# SCH_Proyecto1_2023-10-21.net
KiCad netlist of a schematic drawn in EasyEDA
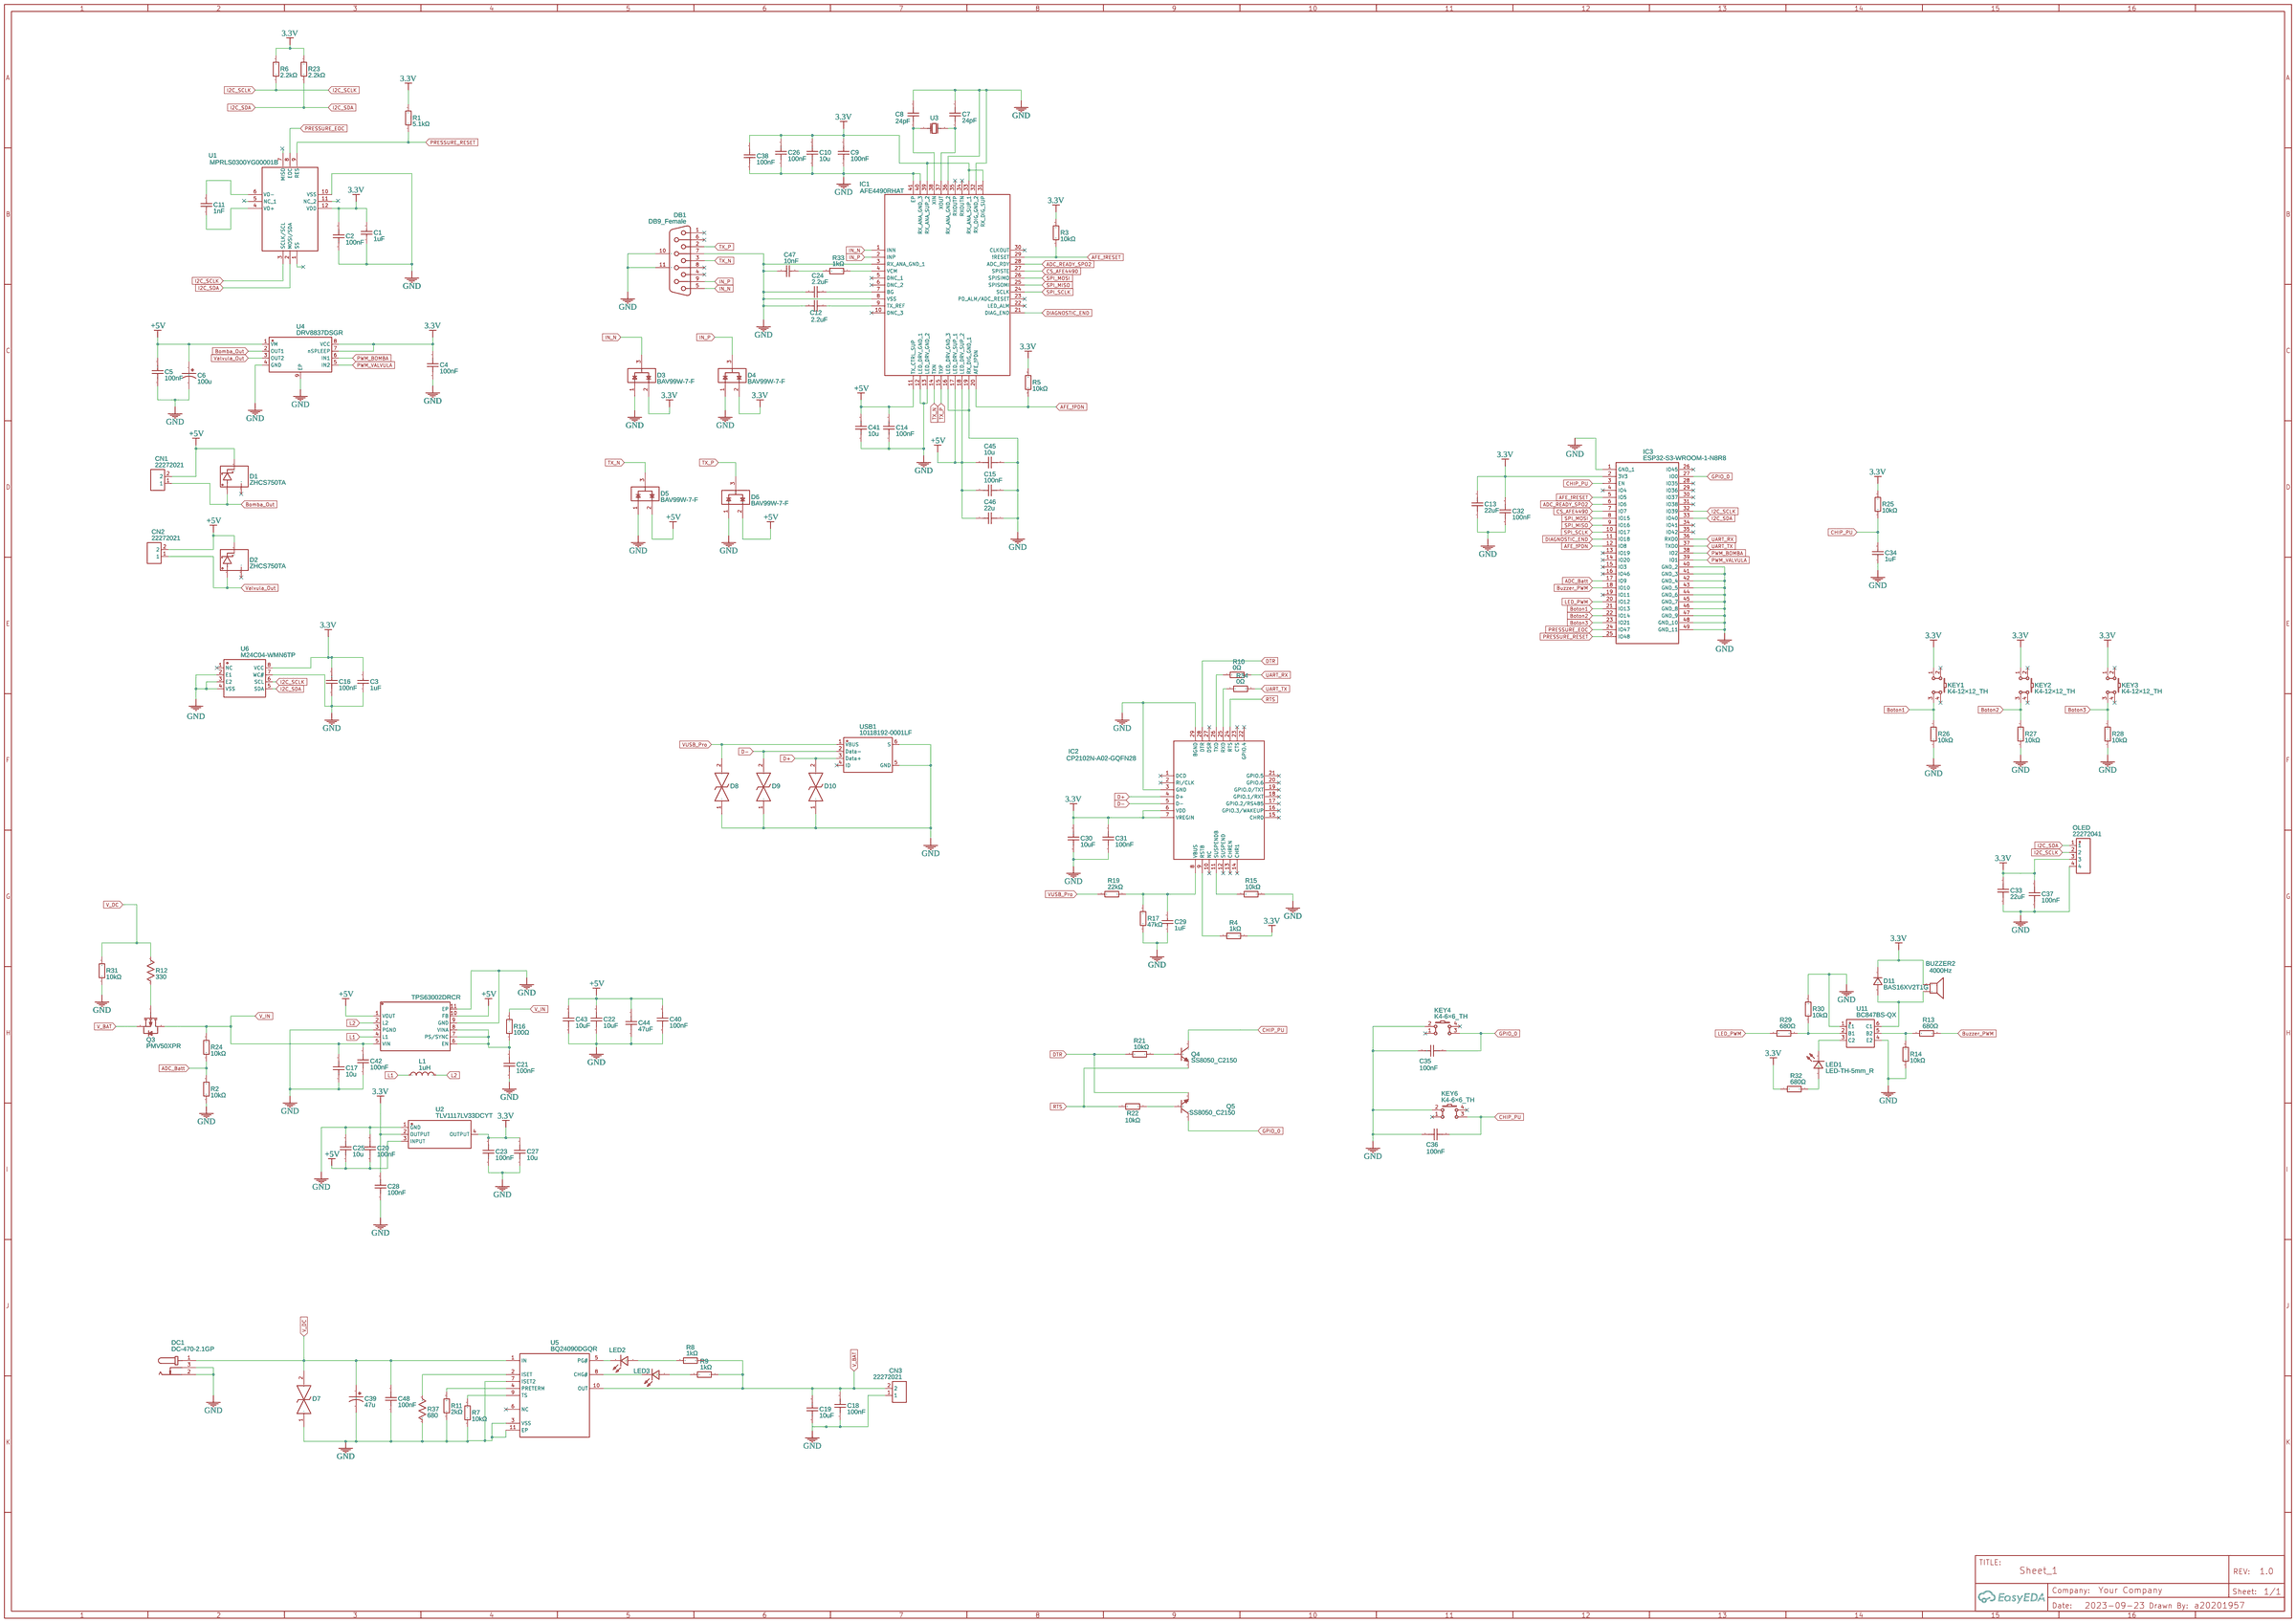
[diagram p0: schematic sheet]

(export (version "E")
  (design (tool "Eeschema 10.0.6"))
  (components
    (comp (ref "BUZZER2")
      (value "4000Hz")
      (fields (field (name "Manufacturer Part") "SFN-1407PA7.6") (field (name "Manufacturer") "S&S(海旭)"))
      (libsource (lib "") (part "SFN-1407PA7.6"))
    )
    (comp (ref "C1")
      (value "1uF")
      (fields
        (field (name "Manufacturer Part") "CL10A105KB8NNNC")
        (field (name "Manufacturer") "SAMSUNG(三星)")
      )
      (libsource (lib "") (part "CL10A105KB8NNNC"))
    )
    (comp (ref "C2")
      (value "100nF")
      (fields
        (field (name "Manufacturer Part") "CC0603KRX7R9BB104")
        (field (name "Manufacturer") "YAGEO(国巨)")
      )
      (libsource (lib "") (part "CC0603KRX7R9BB104"))
    )
    (comp (ref "C3")
      (value "1uF")
      (fields
        (field (name "Manufacturer Part") "CL10A105KB8NNNC")
        (field (name "Manufacturer") "SAMSUNG(三星)")
      )
      (libsource (lib "") (part "CL10A105KB8NNNC"))
    )
    (comp (ref "C4")
      (value "100nF")
      (fields
        (field (name "Manufacturer Part") "CC0603KRX7R9BB104")
        (field (name "Manufacturer") "YAGEO(国巨)")
      )
      (libsource (lib "") (part "CC0603KRX7R9BB104"))
    )
    (comp (ref "C5")
      (value "100nF")
      (fields
        (field (name "Manufacturer Part") "CC0603KRX7R9BB104")
        (field (name "Manufacturer") "YAGEO(国巨)")
      )
      (libsource (lib "") (part "CC0603KRX7R9BB104"))
    )
    (comp (ref "C6") (value "100u") (libsource (lib "") (part "CE_TH_D5.0×F2.0_US_1")))
    (comp (ref "C7") (value "24pF") (libsource (lib "") (part "C_0603_US")))
    (comp (ref "C8") (value "24pF") (libsource (lib "") (part "C_0603_US")))
    (comp (ref "C9")
      (value "100nF")
      (fields
        (field (name "Manufacturer Part") "CC0603KRX7R9BB104")
        (field (name "Manufacturer") "YAGEO(国巨)")
      )
      (libsource (lib "") (part "CC0603KRX7R9BB104"))
    )
    (comp (ref "C10") (value "10u") (libsource (lib "") (part "C_0805_US")))
    (comp (ref "C11")
      (value "1nF")
      (fields
        (field (name "Manufacturer Part") "CL10B102KB8NNNC")
        (field (name "Manufacturer") "SAMSUNG(三星)")
      )
      (libsource (lib "") (part "CL10B102KB8NNNC"))
    )
    (comp (ref "C12")
      (value "2.2uF")
      (fields
        (field (name "Manufacturer Part") "CL10A225KO8NNNC")
        (field (name "Manufacturer") "SAMSUNG(三星)")
      )
      (libsource (lib "") (part "CL10A225KO8NNNC"))
    )
    (comp (ref "C13")
      (value "22uF")
      (fields
        (field (name "Manufacturer Part") "CL21A226MAQNNNE")
        (field (name "Manufacturer") "SAMSUNG(三星)")
      )
      (libsource (lib "") (part "CL21A226MAQNNNE"))
    )
    (comp (ref "C14")
      (value "100nF")
      (fields
        (field (name "Manufacturer Part") "CC0603KRX7R9BB104")
        (field (name "Manufacturer") "YAGEO(国巨)")
      )
      (libsource (lib "") (part "CC0603KRX7R9BB104"))
    )
    (comp (ref "C15")
      (value "100nF")
      (fields
        (field (name "Manufacturer Part") "CC0603KRX7R9BB104")
        (field (name "Manufacturer") "YAGEO(国巨)")
      )
      (libsource (lib "") (part "CC0603KRX7R9BB104_1"))
    )
    (comp (ref "C16")
      (value "100nF")
      (fields
        (field (name "Manufacturer Part") "CC0603KRX7R9BB104")
        (field (name "Manufacturer") "YAGEO(国巨)")
      )
      (libsource (lib "") (part "CC0603KRX7R9BB104"))
    )
    (comp (ref "C17") (value "10u") (libsource (lib "") (part "C_0805_US")))
    (comp (ref "C18")
      (value "100nF")
      (fields
        (field (name "Manufacturer Part") "CC0603KRX7R9BB104")
        (field (name "Manufacturer") "YAGEO(国巨)")
      )
      (libsource (lib "") (part "CC0603KRX7R9BB104"))
    )
    (comp (ref "C19") (value "10uF") (libsource (lib "") (part "C_0805_US")))
    (comp (ref "C20")
      (value "100nF")
      (fields
        (field (name "Manufacturer Part") "CC0603KRX7R9BB104")
        (field (name "Manufacturer") "YAGEO(国巨)")
      )
      (libsource (lib "") (part "CC0603KRX7R9BB104"))
    )
    (comp (ref "C21")
      (value "100nF")
      (fields
        (field (name "Manufacturer Part") "CC0603KRX7R9BB104")
        (field (name "Manufacturer") "YAGEO(国巨)")
      )
      (libsource (lib "") (part "CC0603KRX7R9BB104"))
    )
    (comp (ref "C22") (value "10uF") (libsource (lib "") (part "C_0805_US")))
    (comp (ref "C23")
      (value "100nF")
      (fields
        (field (name "Manufacturer Part") "CC0603KRX7R9BB104")
        (field (name "Manufacturer") "YAGEO(国巨)")
      )
      (libsource (lib "") (part "CC0603KRX7R9BB104"))
    )
    (comp (ref "C24")
      (value "2.2uF")
      (fields
        (field (name "Manufacturer Part") "CL10A225KO8NNNC")
        (field (name "Manufacturer") "SAMSUNG(三星)")
      )
      (libsource (lib "") (part "CL10A225KO8NNNC"))
    )
    (comp (ref "C25") (value "10u") (libsource (lib "") (part "C_0805_US")))
    (comp (ref "C26")
      (value "100nF")
      (fields
        (field (name "Manufacturer Part") "CC0603KRX7R9BB104")
        (field (name "Manufacturer") "YAGEO(国巨)")
      )
      (libsource (lib "") (part "CC0603KRX7R9BB104"))
    )
    (comp (ref "C27") (value "10u") (libsource (lib "") (part "C_0805_US")))
    (comp (ref "C28")
      (value "100nF")
      (fields
        (field (name "Manufacturer Part") "CC0603KRX7R9BB104")
        (field (name "Manufacturer") "YAGEO(国巨)")
      )
      (libsource (lib "") (part "CC0603KRX7R9BB104"))
    )
    (comp (ref "C29")
      (value "1uF")
      (fields
        (field (name "Manufacturer Part") "CL10A105KB8NNNC")
        (field (name "Manufacturer") "SAMSUNG(三星)")
      )
      (libsource (lib "") (part "CL10A105KB8NNNC"))
    )
    (comp (ref "C30") (value "10uF") (libsource (lib "") (part "C_0805_US")))
    (comp (ref "C31")
      (value "100nF")
      (fields
        (field (name "Manufacturer Part") "CC0603KRX7R9BB104")
        (field (name "Manufacturer") "YAGEO(国巨)")
      )
      (libsource (lib "") (part "CC0603KRX7R9BB104"))
    )
    (comp (ref "C32")
      (value "100nF")
      (fields
        (field (name "Manufacturer Part") "CC0603KRX7R9BB104")
        (field (name "Manufacturer") "YAGEO(国巨)")
      )
      (libsource (lib "") (part "CC0603KRX7R9BB104"))
    )
    (comp (ref "C33")
      (value "22uF")
      (fields
        (field (name "Manufacturer Part") "CL21A226MAQNNNE")
        (field (name "Manufacturer") "SAMSUNG(三星)")
      )
      (libsource (lib "") (part "CL21A226MAQNNNE"))
    )
    (comp (ref "C34")
      (value "1uF")
      (fields
        (field (name "Manufacturer Part") "CL10A105KB8NNNC")
        (field (name "Manufacturer") "SAMSUNG(三星)")
      )
      (libsource (lib "") (part "CL10A105KB8NNNC"))
    )
    (comp (ref "C35")
      (value "100nF")
      (fields
        (field (name "Manufacturer Part") "CC0603KRX7R9BB104")
        (field (name "Manufacturer") "YAGEO(国巨)")
      )
      (libsource (lib "") (part "CC0603KRX7R9BB104_1"))
    )
    (comp (ref "C36")
      (value "100nF")
      (fields
        (field (name "Manufacturer Part") "CC0603KRX7R9BB104")
        (field (name "Manufacturer") "YAGEO(国巨)")
      )
      (libsource (lib "") (part "CC0603KRX7R9BB104_1"))
    )
    (comp (ref "C37")
      (value "100nF")
      (fields
        (field (name "Manufacturer Part") "CC0603KRX7R9BB104")
        (field (name "Manufacturer") "YAGEO(国巨)")
      )
      (libsource (lib "") (part "CC0603KRX7R9BB104"))
    )
    (comp (ref "C38")
      (value "100nF")
      (fields
        (field (name "Manufacturer Part") "CC0603KRX7R9BB104")
        (field (name "Manufacturer") "YAGEO(国巨)")
      )
      (libsource (lib "") (part "CC0603KRX7R9BB104"))
    )
    (comp (ref "C39") (value "47u") (libsource (lib "") (part "CE_TH_D5.0×F2.0_US")))
    (comp (ref "C40")
      (value "100nF")
      (fields
        (field (name "Manufacturer Part") "CC0603KRX7R9BB104")
        (field (name "Manufacturer") "YAGEO(国巨)")
      )
      (libsource (lib "") (part "CC0603KRX7R9BB104"))
    )
    (comp (ref "C41") (value "10u") (libsource (lib "") (part "C_0805_US")))
    (comp (ref "C42")
      (value "100nF")
      (fields
        (field (name "Manufacturer Part") "CC0603KRX7R9BB104")
        (field (name "Manufacturer") "YAGEO(国巨)")
      )
      (libsource (lib "") (part "CC0603KRX7R9BB104"))
    )
    (comp (ref "C43") (value "10uF") (libsource (lib "") (part "C_0805_US")))
    (comp (ref "C44")
      (value "47uF")
      (fields
        (field (name "Manufacturer Part") "CL31A476MPHNNNE")
        (field (name "Manufacturer") "SAMSUNG(三星)")
      )
      (libsource (lib "") (part "CL31A476MPHNNNE"))
    )
    (comp (ref "C45") (value "10u") (libsource (lib "") (part "C_0805_US_1")))
    (comp (ref "C46") (value "22u") (libsource (lib "") (part "C_0603_US_1")))
    (comp (ref "C47")
      (value "10nF")
      (fields (field (name "Manufacturer Part") "0603B103K500NT") (field (name "Manufacturer") "FH(风华)"))
      (libsource (lib "") (part "0603B103K500NT"))
    )
    (comp (ref "C48")
      (value "100nF")
      (fields
        (field (name "Manufacturer Part") "CC0603KRX7R9BB104")
        (field (name "Manufacturer") "YAGEO(国巨)")
      )
      (libsource (lib "") (part "CC0603KRX7R9BB104"))
    )
    (comp (ref "CN1")
      (value "22272021")
      (fields (field (name "Manufacturer") "MOLEX"))
      (libsource (lib "") (part "22272021_1"))
    )
    (comp (ref "CN2")
      (value "22272021")
      (fields (field (name "Manufacturer") "MOLEX"))
      (libsource (lib "") (part "22272021_1"))
    )
    (comp (ref "CN3")
      (value "22272021")
      (fields (field (name "Manufacturer") "MOLEX"))
      (libsource (lib "") (part "22272021"))
    )
    (comp (ref "D1")
      (value "ZHCS750TA")
      (fields (field (name "Manufacturer") "DIODES(美台)"))
      (libsource (lib "") (part "ZHCS750TA"))
    )
    (comp (ref "D2")
      (value "ZHCS750TA")
      (fields (field (name "Manufacturer") "DIODES(美台)"))
      (libsource (lib "") (part "ZHCS750TA"))
    )
    (comp (ref "D3")
      (value "BAV99W-7-F")
      (fields (field (name "Manufacturer") "DIODES(美台)"))
      (libsource (lib "") (part "BAV99W-7-F"))
    )
    (comp (ref "D4")
      (value "BAV99W-7-F")
      (fields (field (name "Manufacturer") "DIODES(美台)"))
      (libsource (lib "") (part "BAV99W-7-F"))
    )
    (comp (ref "D5")
      (value "BAV99W-7-F")
      (fields (field (name "Manufacturer") "DIODES(美台)"))
      (libsource (lib "") (part "BAV99W-7-F"))
    )
    (comp (ref "D6")
      (value "BAV99W-7-F")
      (fields (field (name "Manufacturer") "DIODES(美台)"))
      (libsource (lib "") (part "BAV99W-7-F"))
    )
    (comp (ref "D7") (value "CPDQ5V0-HF") (libsource (lib "") (part "CPDQ5V0-HF")))
    (comp (ref "D8") (value "CPDQ5V0-HF") (libsource (lib "") (part "CPDQ5V0-HF")))
    (comp (ref "D9") (value "CPDQ5V0-HF") (libsource (lib "") (part "CPDQ5V0-HF")))
    (comp (ref "D10") (value "CPDQ5V0-HF") (libsource (lib "") (part "CPDQ5V0-HF")))
    (comp (ref "D11")
      (value "BAS16XV2T1G")
      (fields (field (name "Manufacturer") "onsemi(安森美)"))
      (libsource (lib "") (part "BAS16XV2T1G"))
    )
    (comp (ref "DB1")
      (value "DB9_Female")
      (fields (field (name "Manufacturer") "Ckmtw(灿科盟)"))
      (libsource (lib "") (part "DB9_Female"))
    )
    (comp (ref "DC1")
      (value "DC-470-2.1GP")
      (fields (field (name "Manufacturer") "GANGYUAN"))
      (libsource (lib "") (part "DC-470-2.1GP"))
    )
    (comp (ref "IC1") (value "AFE4490RHAT") (libsource (lib "") (part "AFE4490RHAT")))
    (comp (ref "IC2") (value "CP2102N-A02-GQFN28") (libsource (lib "") (part "CP2102N-A02-GQFN28")))
    (comp (ref "IC3") (value "ESP32-S3-WROOM-1-N8R8") (libsource (lib "") (part "ESP32-S3-WROOM-1-N8R8")))
    (comp (ref "KEY1")
      (value "K4-12×12_TH")
      (fields (field (name "Manufacturer Part") "K2-1103DP-M4SW-04") (field (name "Manufacturer") "韩国韩荣"))
      (libsource (lib "") (part "K4-12×12_TH"))
    )
    (comp (ref "KEY2")
      (value "K4-12×12_TH")
      (fields (field (name "Manufacturer Part") "K2-1103DP-M4SW-04") (field (name "Manufacturer") "韩国韩荣"))
      (libsource (lib "") (part "K4-12×12_TH"))
    )
    (comp (ref "KEY3")
      (value "K4-12×12_TH")
      (fields (field (name "Manufacturer Part") "K2-1103DP-M4SW-04") (field (name "Manufacturer") "韩国韩荣"))
      (libsource (lib "") (part "K4-12×12_TH"))
    )
    (comp (ref "KEY4")
      (value "K4-6×6_TH")
      (fields (field (name "Manufacturer Part") "K2-1102DP-E4SW-04") (field (name "Manufacturer") "韩国韩荣"))
      (libsource (lib "") (part "K4-6×6_TH"))
    )
    (comp (ref "KEY6")
      (value "K4-6×6_TH")
      (fields (field (name "Manufacturer Part") "K2-1102DP-E4SW-04") (field (name "Manufacturer") "韩国韩荣"))
      (libsource (lib "") (part "K4-6×6_TH"))
    )
    (comp (ref "L1")
      (value "1uH")
      (fields
        (field (name "Manufacturer Part") "NR3015T1R0N")
        (field (name "Manufacturer") "TAIYO YUDEN(太诱)")
      )
      (libsource (lib "") (part "NR3015T1R0N"))
    )
    (comp (ref "LED1")
      (value "LED-TH-5mm_R")
      (fields
        (field (name "Manufacturer Part") "333-2SURD/S530-A3")
        (field (name "Manufacturer") "EVERLIGHT(台湾亿光)")
      )
      (libsource (lib "") (part "LED-TH-5mm_R"))
    )
    (comp (ref "LED2")
      (value "LED-TH-5mm_R")
      (fields
        (field (name "Manufacturer Part") "333-2SURD/S530-A3")
        (field (name "Manufacturer") "EVERLIGHT(台湾亿光)")
      )
      (libsource (lib "") (part "LED-TH-5mm_R_1"))
    )
    (comp (ref "LED3")
      (value "LED-TH-5mm_G")
      (fields
        (field (name "Manufacturer Part") "333-2SYGD/S530-E2")
        (field (name "Manufacturer") "EVERLIGHT(台湾亿光)")
      )
      (libsource (lib "") (part "LED-TH-5mm_G"))
    )
    (comp (ref "OLED")
      (value "22272041")
      (fields (field (name "Manufacturer") "MOLEX"))
      (libsource (lib "") (part "22272041"))
    )
    (comp (ref "Q3")
      (value "PMV50XPR")
      (fields (field (name "Manufacturer") "Nexperia(安世)"))
      (libsource (lib "") (part "PMV50XPR"))
    )
    (comp (ref "Q4")
      (value "SS8050_C2150")
      (fields (field (name "Manufacturer Part") "SS8050") (field (name "Manufacturer") "CJ(江苏长电/长晶)"))
      (libsource (lib "") (part "SS8050_C2150_1"))
    )
    (comp (ref "Q5")
      (value "SS8050_C2150")
      (fields (field (name "Manufacturer Part") "SS8050") (field (name "Manufacturer") "CJ(江苏长电/长晶)"))
      (libsource (lib "") (part "SS8050_C2150"))
    )
    (comp (ref "R1")
      (value "5.1kΩ")
      (fields
        (field (name "Manufacturer Part") "0603WAF5101T5E")
        (field (name "Manufacturer") "UNI-ROYAL(厚声)")
      )
      (libsource (lib "") (part "0603WAF5101T5E"))
    )
    (comp (ref "R2")
      (value "10kΩ")
      (fields
        (field (name "Manufacturer Part") "0603WAF1002T5E")
        (field (name "Manufacturer") "UNI-ROYAL(厚声)")
      )
      (libsource (lib "") (part "0603WAF1002T5E"))
    )
    (comp (ref "R3")
      (value "10kΩ")
      (fields
        (field (name "Manufacturer Part") "0603WAF1002T5E")
        (field (name "Manufacturer") "UNI-ROYAL(厚声)")
      )
      (libsource (lib "") (part "0603WAF1002T5E"))
    )
    (comp (ref "R4")
      (value "1kΩ")
      (fields
        (field (name "Manufacturer Part") "0603WAF1001T5E")
        (field (name "Manufacturer") "UNI-ROYAL(厚声)")
      )
      (libsource (lib "") (part "0603WAF1001T5E"))
    )
    (comp (ref "R5")
      (value "10kΩ")
      (fields
        (field (name "Manufacturer Part") "0603WAF1002T5E")
        (field (name "Manufacturer") "UNI-ROYAL(厚声)")
      )
      (libsource (lib "") (part "0603WAF1002T5E"))
    )
    (comp (ref "R6")
      (value "2.2kΩ")
      (fields
        (field (name "Manufacturer Part") "0603WAF2201T5E")
        (field (name "Manufacturer") "UNI-ROYAL(厚声)")
      )
      (libsource (lib "") (part "0603WAF2201T5E"))
    )
    (comp (ref "R7")
      (value "10kΩ")
      (fields
        (field (name "Manufacturer Part") "0603WAF1002T5E")
        (field (name "Manufacturer") "UNI-ROYAL(厚声)")
      )
      (libsource (lib "") (part "0603WAF1002T5E"))
    )
    (comp (ref "R8")
      (value "1kΩ")
      (fields
        (field (name "Manufacturer Part") "0603WAF1001T5E")
        (field (name "Manufacturer") "UNI-ROYAL(厚声)")
      )
      (libsource (lib "") (part "0603WAF1001T5E"))
    )
    (comp (ref "R9")
      (value "1kΩ")
      (fields
        (field (name "Manufacturer Part") "0603WAF1001T5E")
        (field (name "Manufacturer") "UNI-ROYAL(厚声)")
      )
      (libsource (lib "") (part "0603WAF1001T5E"))
    )
    (comp (ref "R10")
      (value "0Ω")
      (fields
        (field (name "Manufacturer Part") "1206W4F0000T5E")
        (field (name "Manufacturer") "UNI-ROYAL(厚声)")
      )
      (libsource (lib "") (part "1206W4F0000T5E"))
    )
    (comp (ref "R11")
      (value "2kΩ")
      (fields
        (field (name "Manufacturer Part") "0603WAF2001T5E")
        (field (name "Manufacturer") "UNI-ROYAL(厚声)")
      )
      (libsource (lib "") (part "0603WAF2001T5E"))
    )
    (comp (ref "R12") (value "330") (libsource (lib "") (part "R_1206_US")))
    (comp (ref "R13")
      (value "680Ω")
      (fields
        (field (name "Manufacturer Part") "0603WAF6800T5E")
        (field (name "Manufacturer") "UNI-ROYAL(厚声)")
      )
      (libsource (lib "") (part "0603WAF6800T5E"))
    )
    (comp (ref "R14")
      (value "10kΩ")
      (fields
        (field (name "Manufacturer Part") "0603WAF1002T5E")
        (field (name "Manufacturer") "UNI-ROYAL(厚声)")
      )
      (libsource (lib "") (part "0603WAF1002T5E"))
    )
    (comp (ref "R15")
      (value "10kΩ")
      (fields
        (field (name "Manufacturer Part") "0603WAF1002T5E")
        (field (name "Manufacturer") "UNI-ROYAL(厚声)")
      )
      (libsource (lib "") (part "0603WAF1002T5E_1"))
    )
    (comp (ref "R16")
      (value "100Ω")
      (fields
        (field (name "Manufacturer Part") "1206W4F1000T5E")
        (field (name "Manufacturer") "UNI-ROYAL(厚声)")
      )
      (libsource (lib "") (part "1206W4F1000T5E"))
    )
    (comp (ref "R17")
      (value "47kΩ")
      (fields
        (field (name "Manufacturer Part") "0603WAF4702T5E")
        (field (name "Manufacturer") "UNI-ROYAL(厚声)")
      )
      (libsource (lib "") (part "0603WAF4702T5E"))
    )
    (comp (ref "R19")
      (value "22kΩ")
      (fields
        (field (name "Manufacturer Part") "0603WAF2202T5E")
        (field (name "Manufacturer") "UNI-ROYAL(厚声)")
      )
      (libsource (lib "") (part "0603WAF2202T5E"))
    )
    (comp (ref "R21")
      (value "10kΩ")
      (fields
        (field (name "Manufacturer Part") "0603WAF1002T5E")
        (field (name "Manufacturer") "UNI-ROYAL(厚声)")
      )
      (libsource (lib "") (part "0603WAF1002T5E_1"))
    )
    (comp (ref "R22")
      (value "10kΩ")
      (fields
        (field (name "Manufacturer Part") "0603WAF1002T5E")
        (field (name "Manufacturer") "UNI-ROYAL(厚声)")
      )
      (libsource (lib "") (part "0603WAF1002T5E_1"))
    )
    (comp (ref "R23")
      (value "2.2kΩ")
      (fields
        (field (name "Manufacturer Part") "0603WAF2201T5E")
        (field (name "Manufacturer") "UNI-ROYAL(厚声)")
      )
      (libsource (lib "") (part "0603WAF2201T5E"))
    )
    (comp (ref "R24")
      (value "10kΩ")
      (fields
        (field (name "Manufacturer Part") "0603WAF1002T5E")
        (field (name "Manufacturer") "UNI-ROYAL(厚声)")
      )
      (libsource (lib "") (part "0603WAF1002T5E"))
    )
    (comp (ref "R25")
      (value "10kΩ")
      (fields
        (field (name "Manufacturer Part") "0603WAF1002T5E")
        (field (name "Manufacturer") "UNI-ROYAL(厚声)")
      )
      (libsource (lib "") (part "0603WAF1002T5E"))
    )
    (comp (ref "R26")
      (value "10kΩ")
      (fields
        (field (name "Manufacturer Part") "0603WAF1002T5E")
        (field (name "Manufacturer") "UNI-ROYAL(厚声)")
      )
      (libsource (lib "") (part "0603WAF1002T5E"))
    )
    (comp (ref "R27")
      (value "10kΩ")
      (fields
        (field (name "Manufacturer Part") "0603WAF1002T5E")
        (field (name "Manufacturer") "UNI-ROYAL(厚声)")
      )
      (libsource (lib "") (part "0603WAF1002T5E"))
    )
    (comp (ref "R28")
      (value "10kΩ")
      (fields
        (field (name "Manufacturer Part") "0603WAF1002T5E")
        (field (name "Manufacturer") "UNI-ROYAL(厚声)")
      )
      (libsource (lib "") (part "0603WAF1002T5E"))
    )
    (comp (ref "R29")
      (value "680Ω")
      (fields
        (field (name "Manufacturer Part") "0603WAF6800T5E")
        (field (name "Manufacturer") "UNI-ROYAL(厚声)")
      )
      (libsource (lib "") (part "0603WAF6800T5E"))
    )
    (comp (ref "R30")
      (value "10kΩ")
      (fields
        (field (name "Manufacturer Part") "0603WAF1002T5E")
        (field (name "Manufacturer") "UNI-ROYAL(厚声)")
      )
      (libsource (lib "") (part "0603WAF1002T5E"))
    )
    (comp (ref "R31")
      (value "10kΩ")
      (fields
        (field (name "Manufacturer Part") "0603WAF1002T5E")
        (field (name "Manufacturer") "UNI-ROYAL(厚声)")
      )
      (libsource (lib "") (part "0603WAF1002T5E"))
    )
    (comp (ref "R32")
      (value "680Ω")
      (fields
        (field (name "Manufacturer Part") "0603WAF6800T5E")
        (field (name "Manufacturer") "UNI-ROYAL(厚声)")
      )
      (libsource (lib "") (part "0603WAF6800T5E"))
    )
    (comp (ref "R33")
      (value "1kΩ")
      (fields
        (field (name "Manufacturer Part") "0603WAF1001T5E")
        (field (name "Manufacturer") "UNI-ROYAL(厚声)")
      )
      (libsource (lib "") (part "0603WAF1001T5E"))
    )
    (comp (ref "R34")
      (value "0Ω")
      (fields
        (field (name "Manufacturer Part") "1206W4F0000T5E")
        (field (name "Manufacturer") "UNI-ROYAL(厚声)")
      )
      (libsource (lib "") (part "1206W4F0000T5E"))
    )
    (comp (ref "R37") (value "680") (libsource (lib "") (part "R_1206_US")))
    (comp (ref "U1") (value "MPRLS0300YG00001B") (libsource (lib "") (part "MPRLS0300YG00001B")))
    (comp (ref "U2")
      (value "TLV1117LV33DCYT")
      (fields (field (name "Manufacturer") "TI(德州仪器)"))
      (libsource (lib "") (part "TLV1117LV33DCYT"))
    )
    (comp (ref "U3")
      (value "ECS-80-18-5PLX-AGN-TR")
      (fields (field (name "Manufacturer") "ECS"))
      (libsource (lib "") (part "ECS-80-18-5PLX-AGN-TR"))
    )
    (comp (ref "U4")
      (value "DRV8837DSGR")
      (fields (field (name "Manufacturer") "TI(德州仪器)"))
      (libsource (lib "") (part "DRV8837DSGR"))
    )
    (comp (ref "U5")
      (value "BQ24090DGQR")
      (fields (field (name "Manufacturer") "TI(德州仪器)"))
      (libsource (lib "") (part "BQ24090DGQR"))
    )
    (comp (ref "U6")
      (value "M24C04-WMN6TP")
      (fields (field (name "Manufacturer") "ST(意法半导体)"))
      (libsource (lib "") (part "M24C04-WMN6TP"))
    )
    (comp (ref "U7")
      (value "TPS63002DRCR")
      (fields (field (name "Manufacturer") "TI(德州仪器)"))
      (libsource (lib "") (part "TPS63002DRCR"))
    )
    (comp (ref "U11")
      (value "BC847BS-QX")
      (fields (field (name "Manufacturer") "Nexperia(安世)"))
      (libsource (lib "") (part "BC847BS-QX"))
    )
    (comp (ref "USB1")
      (value "10118192-0001LF")
      (fields (field (name "Manufacturer") "Amphenol"))
      (libsource (lib "") (part "10118192-0001LF"))
    )
  )
  (nets
    (net (code "1") (name "+5V") (class "Default")
      (node (ref "C14") (pin "2") (pinfunction "2_2") (pintype "unspecified"))
      (node (ref "C15") (pin "2") (pinfunction "2_2") (pintype "unspecified"))
      (node (ref "C20") (pin "1") (pinfunction "1_1") (pintype "unspecified"))
      (node (ref "C22") (pin "2") (pinfunction "2_2") (pintype "unspecified"))
      (node (ref "C25") (pin "1") (pinfunction "1_1") (pintype "unspecified"))
      (node (ref "C40") (pin "2") (pinfunction "2_2") (pintype "unspecified"))
      (node (ref "C41") (pin "2") (pinfunction "2_2") (pintype "unspecified"))
      (node (ref "C43") (pin "2") (pinfunction "2_2") (pintype "unspecified"))
      (node (ref "C44") (pin "2") (pinfunction "2_2") (pintype "unspecified"))
      (node (ref "C45") (pin "2") (pinfunction "2_2") (pintype "unspecified"))
      (node (ref "C46") (pin "2") (pinfunction "2_2") (pintype "unspecified"))
      (node (ref "C5") (pin "2") (pinfunction "2_2") (pintype "unspecified"))
      (node (ref "C6") (pin "1") (pinfunction "1_1") (pintype "unspecified"))
      (node (ref "CN1") (pin "2") (pinfunction "2_2") (pintype "unspecified"))
      (node (ref "CN2") (pin "2") (pinfunction "2_2") (pintype "unspecified"))
      (node (ref "D1") (pin "3") (pinfunction "3_3") (pintype "unspecified"))
      (node (ref "D2") (pin "3") (pinfunction "3_3") (pintype "unspecified"))
      (node (ref "D5") (pin "2") (pinfunction "2_2") (pintype "unspecified"))
      (node (ref "D6") (pin "2") (pinfunction "2_2") (pintype "unspecified"))
      (node (ref "IC1") (pin "11") (pinfunction "TX_CTRL_SUP_11") (pintype "bidirectional"))
      (node (ref "IC1") (pin "17") (pinfunction "LED_DRV_SUP_1_17") (pintype "bidirectional"))
      (node (ref "IC1") (pin "18") (pinfunction "LED_DRV_SUP_2_18") (pintype "bidirectional"))
      (node (ref "U2") (pin "3") (pinfunction "INPUT_3") (pintype "unspecified"))
      (node (ref "U4") (pin "1") (pinfunction "VM_1") (pintype "unspecified"))
      (node (ref "U7") (pin "1") (pinfunction "VOUT_1") (pintype "unspecified"))
      (node (ref "U7") (pin "10") (pinfunction "FB_10") (pintype "unspecified"))
    )
    (net (code "2") (name "3.3V") (class "Default")
      (node (ref "BUZZER2") (pin "1") (pinfunction "1_1") (pintype "unspecified"))
      (node (ref "C1") (pin "2") (pinfunction "2_2") (pintype "input"))
      (node (ref "C10") (pin "2") (pinfunction "2_2") (pintype "unspecified"))
      (node (ref "C13") (pin "2") (pinfunction "2_2") (pintype "unspecified"))
      (node (ref "C16") (pin "2") (pinfunction "2_2") (pintype "unspecified"))
      (node (ref "C2") (pin "2") (pinfunction "2_2") (pintype "unspecified"))
      (node (ref "C23") (pin "2") (pinfunction "2_2") (pintype "unspecified"))
      (node (ref "C26") (pin "2") (pinfunction "2_2") (pintype "unspecified"))
      (node (ref "C27") (pin "2") (pinfunction "2_2") (pintype "unspecified"))
      (node (ref "C28") (pin "2") (pinfunction "2_2") (pintype "unspecified"))
      (node (ref "C3") (pin "2") (pinfunction "2_2") (pintype "input"))
      (node (ref "C30") (pin "2") (pinfunction "2_2") (pintype "unspecified"))
      (node (ref "C31") (pin "2") (pinfunction "2_2") (pintype "unspecified"))
      (node (ref "C32") (pin "2") (pinfunction "2_2") (pintype "unspecified"))
      (node (ref "C33") (pin "2") (pinfunction "2_2") (pintype "unspecified"))
      (node (ref "C37") (pin "2") (pinfunction "2_2") (pintype "unspecified"))
      (node (ref "C38") (pin "2") (pinfunction "2_2") (pintype "unspecified"))
      (node (ref "C4") (pin "2") (pinfunction "2_2") (pintype "unspecified"))
      (node (ref "C9") (pin "2") (pinfunction "2_2") (pintype "unspecified"))
      (node (ref "D11") (pin "1") (pinfunction "C_1") (pintype "unspecified"))
      (node (ref "D3") (pin "2") (pinfunction "2_2") (pintype "unspecified"))
      (node (ref "D4") (pin "2") (pinfunction "2_2") (pintype "unspecified"))
      (node (ref "IC1") (pin "31") (pinfunction "RX_DIG_SUP_31") (pintype "bidirectional"))
      (node (ref "IC1") (pin "33") (pinfunction "RX_ANA_SUP_1_33") (pintype "bidirectional"))
      (node (ref "IC1") (pin "39") (pinfunction "RX_ANA_SUP_2_39") (pintype "bidirectional"))
      (node (ref "IC2") (pin "6") (pinfunction "VDD_6") (pintype "bidirectional"))
      (node (ref "IC2") (pin "7") (pinfunction "VREGIN_7") (pintype "bidirectional"))
      (node (ref "IC3") (pin "2") (pinfunction "3V3_2") (pintype "bidirectional"))
      (node (ref "KEY1") (pin "1") (pinfunction "1_1") (pintype "unspecified"))
      (node (ref "KEY2") (pin "1") (pinfunction "1_1") (pintype "unspecified"))
      (node (ref "KEY3") (pin "1") (pinfunction "1_1") (pintype "unspecified"))
      (node (ref "OLED") (pin "3") (pinfunction "3_3") (pintype "unspecified"))
      (node (ref "R1") (pin "2") (pinfunction "2_2") (pintype "input"))
      (node (ref "R23") (pin "2") (pinfunction "2_2") (pintype "input"))
      (node (ref "R25") (pin "2") (pinfunction "2_2") (pintype "input"))
      (node (ref "R3") (pin "2") (pinfunction "2_2") (pintype "input"))
      (node (ref "R32") (pin "1") (pinfunction "1_1") (pintype "input"))
      (node (ref "R4") (pin "1") (pinfunction "1_1") (pintype "input"))
      (node (ref "R5") (pin "2") (pinfunction "2_2") (pintype "input"))
      (node (ref "R6") (pin "2") (pinfunction "2_2") (pintype "input"))
      (node (ref "U1") (pin "12") (pinfunction "VDD_12") (pintype "bidirectional"))
      (node (ref "U2") (pin "2") (pinfunction "OUTPUT_2") (pintype "unspecified"))
      (node (ref "U2") (pin "4") (pinfunction "OUTPUT_4") (pintype "unspecified"))
      (node (ref "U4") (pin "7") (pinfunction "nSPLEEP_7") (pintype "unspecified"))
      (node (ref "U4") (pin "8") (pinfunction "VCC_8") (pintype "unspecified"))
      (node (ref "U6") (pin "8") (pinfunction "VCC_8") (pintype "unspecified"))
    )
    (net (code "3") (name "ADC_Batt") (class "Default")
      (node (ref "IC3") (pin "17") (pinfunction "IO9_17") (pintype "bidirectional"))
      (node (ref "R2") (pin "2") (pinfunction "2_2") (pintype "input"))
      (node (ref "R24") (pin "1") (pinfunction "1_1") (pintype "input"))
    )
    (net (code "4") (name "ADC_READY_SPO2") (class "Default")
      (node (ref "IC1") (pin "28") (pinfunction "ADC_RDY_28") (pintype "bidirectional"))
      (node (ref "IC3") (pin "6") (pinfunction "IO6_6") (pintype "bidirectional"))
    )
    (net (code "5") (name "AFE_!PDN") (class "Default")
      (node (ref "IC1") (pin "20") (pinfunction "AFE_!PDN_20") (pintype "bidirectional"))
      (node (ref "IC3") (pin "12") (pinfunction "IO8_12") (pintype "bidirectional"))
      (node (ref "R5") (pin "1") (pinfunction "1_1") (pintype "input"))
    )
    (net (code "6") (name "AFE_!RESET") (class "Default")
      (node (ref "IC1") (pin "29") (pinfunction "!RESET_29") (pintype "bidirectional"))
      (node (ref "IC3") (pin "5") (pinfunction "IO5_5") (pintype "bidirectional"))
      (node (ref "R3") (pin "1") (pinfunction "1_1") (pintype "input"))
    )
    (net (code "7") (name "Bomba_Out") (class "Default")
      (node (ref "CN1") (pin "1") (pinfunction "1_1") (pintype "unspecified"))
      (node (ref "D1") (pin "1") (pinfunction "1_1") (pintype "unspecified"))
      (node (ref "U4") (pin "2") (pinfunction "OUT1_2") (pintype "unspecified"))
    )
    (net (code "8") (name "Boton1") (class "Default")
      (node (ref "IC3") (pin "21") (pinfunction "IO13_21") (pintype "bidirectional"))
      (node (ref "KEY1") (pin "3") (pinfunction "3_3") (pintype "unspecified"))
      (node (ref "R26") (pin "2") (pinfunction "2_2") (pintype "input"))
    )
    (net (code "9") (name "Boton2") (class "Default")
      (node (ref "IC3") (pin "22") (pinfunction "IO14_22") (pintype "bidirectional"))
      (node (ref "KEY2") (pin "3") (pinfunction "3_3") (pintype "unspecified"))
      (node (ref "R27") (pin "2") (pinfunction "2_2") (pintype "input"))
    )
    (net (code "10") (name "Boton3") (class "Default")
      (node (ref "IC3") (pin "23") (pinfunction "IO21_23") (pintype "bidirectional"))
      (node (ref "KEY3") (pin "3") (pinfunction "3_3") (pintype "unspecified"))
      (node (ref "R28") (pin "2") (pinfunction "2_2") (pintype "input"))
    )
    (net (code "11") (name "Buzzer_PWM") (class "Default")
      (node (ref "IC3") (pin "18") (pinfunction "IO10_18") (pintype "bidirectional"))
      (node (ref "R13") (pin "2") (pinfunction "2_2") (pintype "input"))
    )
    (net (code "12") (name "CHIP_PU") (class "Default")
      (node (ref "C34") (pin "2") (pinfunction "2_2") (pintype "input"))
      (node (ref "C36") (pin "1") (pinfunction "1_1") (pintype "unspecified"))
      (node (ref "IC3") (pin "3") (pinfunction "EN_3") (pintype "bidirectional"))
      (node (ref "KEY6") (pin "3") (pinfunction "3_3") (pintype "unspecified"))
      (node (ref "Q4") (pin "3") (pinfunction "C_3") (pintype "unspecified"))
      (node (ref "R25") (pin "1") (pinfunction "1_1") (pintype "input"))
    )
    (net (code "13") (name "CS_AFE4490") (class "Default")
      (node (ref "IC1") (pin "27") (pinfunction "SPISTE_27") (pintype "bidirectional"))
      (node (ref "IC3") (pin "7") (pinfunction "IO7_7") (pintype "bidirectional"))
    )
    (net (code "14") (name "D+") (class "Default")
      (node (ref "D10") (pin "2") (pinfunction "2_2") (pintype "bidirectional"))
      (node (ref "IC2") (pin "4") (pinfunction "D+_4") (pintype "bidirectional"))
      (node (ref "USB1") (pin "3") (pinfunction "Data+_3") (pintype "unspecified"))
    )
    (net (code "15") (name "D-") (class "Default")
      (node (ref "D9") (pin "2") (pinfunction "2_2") (pintype "bidirectional"))
      (node (ref "IC2") (pin "5") (pinfunction "D-_5") (pintype "bidirectional"))
      (node (ref "USB1") (pin "2") (pinfunction "Data-_2") (pintype "unspecified"))
    )
    (net (code "16") (name "DIAGNOSTIC_END") (class "Default")
      (node (ref "IC1") (pin "21") (pinfunction "DIAG_END_21") (pintype "bidirectional"))
      (node (ref "IC3") (pin "11") (pinfunction "IO18_11") (pintype "bidirectional"))
    )
    (net (code "17") (name "DTR") (class "Default")
      (node (ref "IC2") (pin "28") (pinfunction "DTR_28") (pintype "bidirectional"))
      (node (ref "Q5") (pin "2") (pinfunction "E_2") (pintype "unspecified"))
      (node (ref "R21") (pin "2") (pinfunction "2_2") (pintype "input"))
    )
    (net (code "18") (name "GND") (class "Default")
      (node (ref "C1") (pin "1") (pinfunction "1_1") (pintype "input"))
      (node (ref "C10") (pin "1") (pinfunction "1_1") (pintype "unspecified"))
      (node (ref "C12") (pin "1") (pinfunction "1_1") (pintype "input"))
      (node (ref "C13") (pin "1") (pinfunction "1_1") (pintype "unspecified"))
      (node (ref "C14") (pin "1") (pinfunction "1_1") (pintype "unspecified"))
      (node (ref "C15") (pin "1") (pinfunction "1_1") (pintype "unspecified"))
      (node (ref "C16") (pin "1") (pinfunction "1_1") (pintype "unspecified"))
      (node (ref "C17") (pin "1") (pinfunction "1_1") (pintype "unspecified"))
      (node (ref "C18") (pin "1") (pinfunction "1_1") (pintype "unspecified"))
      (node (ref "C19") (pin "1") (pinfunction "1_1") (pintype "unspecified"))
      (node (ref "C2") (pin "1") (pinfunction "1_1") (pintype "unspecified"))
      (node (ref "C20") (pin "2") (pinfunction "2_2") (pintype "unspecified"))
      (node (ref "C21") (pin "1") (pinfunction "1_1") (pintype "unspecified"))
      (node (ref "C22") (pin "1") (pinfunction "1_1") (pintype "unspecified"))
      (node (ref "C23") (pin "1") (pinfunction "1_1") (pintype "unspecified"))
      (node (ref "C24") (pin "1") (pinfunction "1_1") (pintype "input"))
      (node (ref "C25") (pin "2") (pinfunction "2_2") (pintype "unspecified"))
      (node (ref "C26") (pin "1") (pinfunction "1_1") (pintype "unspecified"))
      (node (ref "C27") (pin "1") (pinfunction "1_1") (pintype "unspecified"))
      (node (ref "C28") (pin "1") (pinfunction "1_1") (pintype "unspecified"))
      (node (ref "C29") (pin "1") (pinfunction "1_1") (pintype "input"))
      (node (ref "C3") (pin "1") (pinfunction "1_1") (pintype "input"))
      (node (ref "C30") (pin "1") (pinfunction "1_1") (pintype "unspecified"))
      (node (ref "C31") (pin "1") (pinfunction "1_1") (pintype "unspecified"))
      (node (ref "C32") (pin "1") (pinfunction "1_1") (pintype "unspecified"))
      (node (ref "C33") (pin "1") (pinfunction "1_1") (pintype "unspecified"))
      (node (ref "C34") (pin "1") (pinfunction "1_1") (pintype "input"))
      (node (ref "C35") (pin "2") (pinfunction "2_2") (pintype "unspecified"))
      (node (ref "C36") (pin "2") (pinfunction "2_2") (pintype "unspecified"))
      (node (ref "C37") (pin "1") (pinfunction "1_1") (pintype "unspecified"))
      (node (ref "C38") (pin "1") (pinfunction "1_1") (pintype "unspecified"))
      (node (ref "C39") (pin "2") (pinfunction "2_2") (pintype "unspecified"))
      (node (ref "C4") (pin "1") (pinfunction "1_1") (pintype "unspecified"))
      (node (ref "C40") (pin "1") (pinfunction "1_1") (pintype "unspecified"))
      (node (ref "C41") (pin "1") (pinfunction "1_1") (pintype "unspecified"))
      (node (ref "C42") (pin "1") (pinfunction "1_1") (pintype "unspecified"))
      (node (ref "C43") (pin "1") (pinfunction "1_1") (pintype "unspecified"))
      (node (ref "C44") (pin "1") (pinfunction "1_1") (pintype "unspecified"))
      (node (ref "C45") (pin "1") (pinfunction "1_1") (pintype "unspecified"))
      (node (ref "C46") (pin "1") (pinfunction "1_1") (pintype "unspecified"))
      (node (ref "C47") (pin "1") (pinfunction "1_1") (pintype "input"))
      (node (ref "C48") (pin "1") (pinfunction "1_1") (pintype "unspecified"))
      (node (ref "C5") (pin "1") (pinfunction "1_1") (pintype "unspecified"))
      (node (ref "C6") (pin "2") (pinfunction "2_2") (pintype "unspecified"))
      (node (ref "C7") (pin "2") (pinfunction "2_2") (pintype "unspecified"))
      (node (ref "C8") (pin "2") (pinfunction "2_2") (pintype "unspecified"))
      (node (ref "C9") (pin "1") (pinfunction "1_1") (pintype "unspecified"))
      (node (ref "CN3") (pin "1") (pinfunction "1_1") (pintype "unspecified"))
      (node (ref "D10") (pin "1") (pinfunction "1_1") (pintype "bidirectional"))
      (node (ref "D3") (pin "1") (pinfunction "1_1") (pintype "unspecified"))
      (node (ref "D4") (pin "1") (pinfunction "1_1") (pintype "unspecified"))
      (node (ref "D5") (pin "1") (pinfunction "1_1") (pintype "unspecified"))
      (node (ref "D6") (pin "1") (pinfunction "1_1") (pintype "unspecified"))
      (node (ref "D7") (pin "1") (pinfunction "1_1") (pintype "bidirectional"))
      (node (ref "D8") (pin "1") (pinfunction "1_1") (pintype "bidirectional"))
      (node (ref "D9") (pin "1") (pinfunction "1_1") (pintype "bidirectional"))
      (node (ref "DB1") (pin "10") (pinfunction "MH1_10") (pintype "input"))
      (node (ref "DB1") (pin "11") (pinfunction "MH2_11") (pintype "input"))
      (node (ref "DB1") (pin "7") (pinfunction "7_7") (pintype "input"))
      (node (ref "DC1") (pin "2") (pinfunction "2_2") (pintype "unspecified"))
      (node (ref "DC1") (pin "3") (pinfunction "3_3") (pintype "unspecified"))
      (node (ref "IC1") (pin "12") (pinfunction "LED_DRV_GND_1_12") (pintype "bidirectional"))
      (node (ref "IC1") (pin "13") (pinfunction "LED_DRV_GND_2_13") (pintype "bidirectional"))
      (node (ref "IC1") (pin "16") (pinfunction "LED_DRV_GND_3_16") (pintype "bidirectional"))
      (node (ref "IC1") (pin "19") (pinfunction "RX_DIG_GND_1_19") (pintype "bidirectional"))
      (node (ref "IC1") (pin "3") (pinfunction "RX_ANA_GND_1_3") (pintype "bidirectional"))
      (node (ref "IC1") (pin "32") (pinfunction "RX_DIG_GND_2_32") (pintype "bidirectional"))
      (node (ref "IC1") (pin "36") (pinfunction "RX_ANA_GND_2_36") (pintype "bidirectional"))
      (node (ref "IC1") (pin "40") (pinfunction "RX_ANA_GND_3_40") (pintype "bidirectional"))
      (node (ref "IC1") (pin "41") (pinfunction "EP_41") (pintype "bidirectional"))
      (node (ref "IC1") (pin "8") (pinfunction "VSS_8") (pintype "bidirectional"))
      (node (ref "IC2") (pin "29") (pinfunction "BGND_29") (pintype "bidirectional"))
      (node (ref "IC2") (pin "3") (pinfunction "GND_3") (pintype "bidirectional"))
      (node (ref "IC3") (pin "1") (pinfunction "GND_1_1") (pintype "bidirectional"))
      (node (ref "IC3") (pin "40") (pinfunction "GND_2_40") (pintype "bidirectional"))
      (node (ref "IC3") (pin "41") (pinfunction "GND_3_41") (pintype "bidirectional"))
      (node (ref "IC3") (pin "42") (pinfunction "GND_4_42") (pintype "bidirectional"))
      (node (ref "IC3") (pin "43") (pinfunction "GND_5_43") (pintype "bidirectional"))
      (node (ref "IC3") (pin "44") (pinfunction "GND_6_44") (pintype "bidirectional"))
      (node (ref "IC3") (pin "45") (pinfunction "GND_7_45") (pintype "bidirectional"))
      (node (ref "IC3") (pin "46") (pinfunction "GND_8_46") (pintype "bidirectional"))
      (node (ref "IC3") (pin "47") (pinfunction "GND_9_47") (pintype "bidirectional"))
      (node (ref "IC3") (pin "48") (pinfunction "GND_10_48") (pintype "bidirectional"))
      (node (ref "IC3") (pin "49") (pinfunction "GND_11_49") (pintype "bidirectional"))
      (node (ref "KEY4") (pin "2") (pinfunction "2_2") (pintype "unspecified"))
      (node (ref "KEY6") (pin "2") (pinfunction "2_2") (pintype "unspecified"))
      (node (ref "OLED") (pin "4") (pinfunction "4_4") (pintype "unspecified"))
      (node (ref "R11") (pin "1") (pinfunction "1_1") (pintype "input"))
      (node (ref "R14") (pin "1") (pinfunction "1_1") (pintype "input"))
      (node (ref "R15") (pin "1") (pinfunction "1_1") (pintype "input"))
      (node (ref "R17") (pin "1") (pinfunction "1_1") (pintype "input"))
      (node (ref "R2") (pin "1") (pinfunction "1_1") (pintype "input"))
      (node (ref "R26") (pin "1") (pinfunction "1_1") (pintype "input"))
      (node (ref "R27") (pin "1") (pinfunction "1_1") (pintype "input"))
      (node (ref "R28") (pin "1") (pinfunction "1_1") (pintype "input"))
      (node (ref "R30") (pin "2") (pinfunction "2_2") (pintype "input"))
      (node (ref "R31") (pin "1") (pinfunction "1_1") (pintype "input"))
      (node (ref "R37") (pin "1") (pinfunction "1_1") (pintype "unspecified"))
      (node (ref "R7") (pin "1") (pinfunction "1_1") (pintype "input"))
      (node (ref "U1") (pin "10") (pinfunction "VSS_10") (pintype "bidirectional"))
      (node (ref "U11") (pin "1") (pinfunction "E1_1") (pintype "unspecified"))
      (node (ref "U11") (pin "4") (pinfunction "E2_4") (pintype "unspecified"))
      (node (ref "U2") (pin "1") (pinfunction "GND_1") (pintype "unspecified"))
      (node (ref "U4") (pin "4") (pinfunction "GND_4") (pintype "unspecified"))
      (node (ref "U4") (pin "9") (pinfunction "EP_9") (pintype "unspecified"))
      (node (ref "U5") (pin "11") (pinfunction "EP_11") (pintype "unspecified"))
      (node (ref "U5") (pin "3") (pinfunction "VSS_3") (pintype "unspecified"))
      (node (ref "U5") (pin "7") (pinfunction "ISET2_7") (pintype "input"))
      (node (ref "U6") (pin "2") (pinfunction "E1_2") (pintype "unspecified"))
      (node (ref "U6") (pin "3") (pinfunction "E2_3") (pintype "unspecified"))
      (node (ref "U6") (pin "4") (pinfunction "VSS_4") (pintype "unspecified"))
      (node (ref "U6") (pin "7") (pinfunction "WC#_7") (pintype "unspecified"))
      (node (ref "U7") (pin "11") (pinfunction "EP_11") (pintype "unspecified"))
      (node (ref "U7") (pin "3") (pinfunction "PGND_3") (pintype "unspecified"))
      (node (ref "U7") (pin "9") (pinfunction "GND_9") (pintype "unspecified"))
      (node (ref "USB1") (pin "5") (pinfunction "GND_5") (pintype "unspecified"))
      (node (ref "USB1") (pin "6") (pinfunction "S_6") (pintype "unspecified"))
    )
    (net (code "19") (name "GPIO_0") (class "Default")
      (node (ref "C35") (pin "1") (pinfunction "1_1") (pintype "unspecified"))
      (node (ref "IC3") (pin "27") (pinfunction "IO0_27") (pintype "bidirectional"))
      (node (ref "KEY4") (pin "3") (pinfunction "3_3") (pintype "unspecified"))
      (node (ref "Q5") (pin "3") (pinfunction "C_3") (pintype "unspecified"))
    )
    (net (code "20") (name "I2C_SCLK") (class "Default")
      (node (ref "IC3") (pin "32") (pinfunction "IO39_32") (pintype "bidirectional"))
      (node (ref "OLED") (pin "2") (pinfunction "2_2") (pintype "unspecified"))
      (node (ref "R6") (pin "1") (pinfunction "1_1") (pintype "input"))
      (node (ref "U1") (pin "3") (pinfunction "SCLK/SCL_3") (pintype "bidirectional"))
      (node (ref "U6") (pin "6") (pinfunction "SCL_6") (pintype "unspecified"))
    )
    (net (code "21") (name "I2C_SDA") (class "Default")
      (node (ref "IC3") (pin "33") (pinfunction "IO40_33") (pintype "bidirectional"))
      (node (ref "OLED") (pin "1") (pinfunction "1_1") (pintype "unspecified"))
      (node (ref "R23") (pin "1") (pinfunction "1_1") (pintype "input"))
      (node (ref "U1") (pin "2") (pinfunction "MOSI/SDA_2") (pintype "bidirectional"))
      (node (ref "U6") (pin "5") (pinfunction "SDA_5") (pintype "unspecified"))
    )
    (net (code "22") (name "IN_N") (class "Default")
      (node (ref "D3") (pin "3") (pinfunction "3_3") (pintype "unspecified"))
      (node (ref "DB1") (pin "5") (pinfunction "5_5") (pintype "input"))
      (node (ref "IC1") (pin "1") (pinfunction "INN_1") (pintype "bidirectional"))
    )
    (net (code "23") (name "IN_P") (class "Default")
      (node (ref "D4") (pin "3") (pinfunction "3_3") (pintype "unspecified"))
      (node (ref "DB1") (pin "9") (pinfunction "9_9") (pintype "input"))
      (node (ref "IC1") (pin "2") (pinfunction "INP_2") (pintype "bidirectional"))
    )
    (net (code "24") (name "L1") (class "Default")
      (node (ref "L1") (pin "1") (pinfunction "1_1") (pintype "unspecified"))
      (node (ref "U7") (pin "4") (pinfunction "L1_4") (pintype "unspecified"))
    )
    (net (code "25") (name "L2") (class "Default")
      (node (ref "L1") (pin "2") (pinfunction "2_2") (pintype "unspecified"))
      (node (ref "U7") (pin "2") (pinfunction "L2_2") (pintype "unspecified"))
    )
    (net (code "26") (name "LED_PWM") (class "Default")
      (node (ref "IC3") (pin "20") (pinfunction "IO12_20") (pintype "bidirectional"))
      (node (ref "R29") (pin "1") (pinfunction "1_1") (pintype "input"))
    )
    (net (code "27") (name "Net-(C47-Pad2)") (class "Default")
      (node (ref "C47") (pin "2") (pinfunction "2_2") (pintype "input"))
      (node (ref "R33") (pin "2") (pinfunction "2_2") (pintype "input"))
    )
    (net (code "28") (name "Net-(D11-A)") (class "Default")
      (node (ref "BUZZER2") (pin "2") (pinfunction "2_2") (pintype "unspecified"))
      (node (ref "D11") (pin "2") (pinfunction "A_2") (pintype "unspecified"))
      (node (ref "U11") (pin "6") (pinfunction "C1_6") (pintype "unspecified"))
    )
    (net (code "29") (name "Net-(IC1-BG)") (class "Default")
      (node (ref "C24") (pin "2") (pinfunction "2_2") (pintype "input"))
      (node (ref "IC1") (pin "7") (pinfunction "BG_7") (pintype "bidirectional"))
    )
    (net (code "30") (name "Net-(IC1-TX_REF)") (class "Default")
      (node (ref "C12") (pin "2") (pinfunction "2_2") (pintype "input"))
      (node (ref "IC1") (pin "9") (pinfunction "TX_REF_9") (pintype "bidirectional"))
    )
    (net (code "31") (name "Net-(IC1-VCM)") (class "Default")
      (node (ref "IC1") (pin "4") (pinfunction "VCM_4") (pintype "bidirectional"))
      (node (ref "R33") (pin "1") (pinfunction "1_1") (pintype "input"))
    )
    (net (code "32") (name "Net-(IC1-XIN)") (class "Default")
      (node (ref "C8") (pin "1") (pinfunction "1_1") (pintype "unspecified"))
      (node (ref "IC1") (pin "38") (pinfunction "XIN_38") (pintype "bidirectional"))
      (node (ref "U3") (pin "1") (pinfunction "OSC1_1") (pintype "input"))
    )
    (net (code "33") (name "Net-(IC1-XOUT)") (class "Default")
      (node (ref "C7") (pin "1") (pinfunction "1_1") (pintype "unspecified"))
      (node (ref "IC1") (pin "37") (pinfunction "XOUT_37") (pintype "bidirectional"))
      (node (ref "U3") (pin "2") (pinfunction "OSC2_2") (pintype "input"))
    )
    (net (code "34") (name "Net-(IC2-RSTB)") (class "Default")
      (node (ref "IC2") (pin "9") (pinfunction "RSTB_9") (pintype "bidirectional"))
      (node (ref "R4") (pin "2") (pinfunction "2_2") (pintype "input"))
    )
    (net (code "35") (name "Net-(IC2-RXD)") (class "Default")
      (node (ref "IC2") (pin "25") (pinfunction "RXD_25") (pintype "bidirectional"))
      (node (ref "R34") (pin "1") (pinfunction "1_1") (pintype "input"))
    )
    (net (code "36") (name "Net-(IC2-SUSPENDB)") (class "Default")
      (node (ref "IC2") (pin "11") (pinfunction "SUSPENDB_11") (pintype "bidirectional"))
      (node (ref "R15") (pin "2") (pinfunction "2_2") (pintype "input"))
    )
    (net (code "37") (name "Net-(IC2-TXD)") (class "Default")
      (node (ref "IC2") (pin "26") (pinfunction "TXD_26") (pintype "bidirectional"))
      (node (ref "R10") (pin "1") (pinfunction "1_1") (pintype "input"))
    )
    (net (code "38") (name "Net-(IC2-VBUS)") (class "Default")
      (node (ref "C29") (pin "2") (pinfunction "2_2") (pintype "input"))
      (node (ref "IC2") (pin "8") (pinfunction "VBUS_8") (pintype "bidirectional"))
      (node (ref "R17") (pin "2") (pinfunction "2_2") (pintype "input"))
      (node (ref "R19") (pin "1") (pinfunction "1_1") (pintype "input"))
    )
    (net (code "39") (name "Net-(LED1-Pad1)") (class "Default")
      (node (ref "LED1") (pin "1") (pinfunction "1_1") (pintype "unspecified"))
      (node (ref "R32") (pin "2") (pinfunction "2_2") (pintype "input"))
    )
    (net (code "40") (name "Net-(LED2-Pad1)") (class "Default")
      (node (ref "LED2") (pin "1") (pinfunction "1_1") (pintype "unspecified"))
      (node (ref "R8") (pin "2") (pinfunction "2_2") (pintype "input"))
    )
    (net (code "41") (name "Net-(LED3-Pad1)") (class "Default")
      (node (ref "LED3") (pin "1") (pinfunction "1_1") (pintype "unspecified"))
      (node (ref "R9") (pin "2") (pinfunction "2_2") (pintype "input"))
    )
    (net (code "42") (name "Net-(Q3-G)") (class "Default")
      (node (ref "Q3") (pin "1") (pinfunction "G_1") (pintype "unspecified"))
      (node (ref "R12") (pin "1") (pinfunction "1_1") (pintype "unspecified"))
    )
    (net (code "43") (name "Net-(Q4-B)") (class "Default")
      (node (ref "Q4") (pin "1") (pinfunction "B_1") (pintype "unspecified"))
      (node (ref "R21") (pin "1") (pinfunction "1_1") (pintype "input"))
    )
    (net (code "44") (name "Net-(Q5-B)") (class "Default")
      (node (ref "Q5") (pin "1") (pinfunction "B_1") (pintype "unspecified"))
      (node (ref "R22") (pin "1") (pinfunction "1_1") (pintype "input"))
    )
    (net (code "45") (name "Net-(U1-VO+)") (class "Default")
      (node (ref "C11") (pin "1") (pinfunction "1_1") (pintype "input"))
      (node (ref "U1") (pin "4") (pinfunction "VO+_4") (pintype "bidirectional"))
    )
    (net (code "46") (name "Net-(U1-VO-)") (class "Default")
      (node (ref "C11") (pin "2") (pinfunction "2_2") (pintype "input"))
      (node (ref "U1") (pin "6") (pinfunction "VO-_6") (pintype "bidirectional"))
    )
    (net (code "47") (name "Net-(U5-CHG#)") (class "Default")
      (node (ref "LED3") (pin "2") (pinfunction "2_2") (pintype "unspecified"))
      (node (ref "U5") (pin "8") (pinfunction "CHG#_8") (pintype "output"))
    )
    (net (code "48") (name "Net-(U5-ISET)") (class "Default")
      (node (ref "R37") (pin "2") (pinfunction "2_2") (pintype "unspecified"))
      (node (ref "U5") (pin "2") (pinfunction "ISET_2") (pintype "input"))
    )
    (net (code "49") (name "Net-(U5-PG#)") (class "Default")
      (node (ref "LED2") (pin "2") (pinfunction "2_2") (pintype "unspecified"))
      (node (ref "U5") (pin "5") (pinfunction "PG#_5") (pintype "output"))
    )
    (net (code "50") (name "Net-(U5-PRETERM)") (class "Default")
      (node (ref "R11") (pin "2") (pinfunction "2_2") (pintype "input"))
      (node (ref "U5") (pin "4") (pinfunction "PRETERM_4") (pintype "input"))
    )
    (net (code "51") (name "Net-(U5-TS)") (class "Default")
      (node (ref "R7") (pin "2") (pinfunction "2_2") (pintype "input"))
      (node (ref "U5") (pin "9") (pinfunction "TS_9") (pintype "input"))
    )
    (net (code "52") (name "Net-(U7-EN)") (class "Default")
      (node (ref "C21") (pin "2") (pinfunction "2_2") (pintype "unspecified"))
      (node (ref "R16") (pin "1") (pinfunction "1_1") (pintype "input"))
      (node (ref "U7") (pin "6") (pinfunction "EN_6") (pintype "unspecified"))
      (node (ref "U7") (pin "7") (pinfunction "PS/SYNC_7") (pintype "unspecified"))
      (node (ref "U7") (pin "8") (pinfunction "VINA_8") (pintype "unspecified"))
    )
    (net (code "53") (name "Net-(U11-B1)") (class "Default")
      (node (ref "R29") (pin "2") (pinfunction "2_2") (pintype "input"))
      (node (ref "R30") (pin "1") (pinfunction "1_1") (pintype "input"))
      (node (ref "U11") (pin "2") (pinfunction "B1_2") (pintype "unspecified"))
    )
    (net (code "54") (name "Net-(U11-B2)") (class "Default")
      (node (ref "R13") (pin "1") (pinfunction "1_1") (pintype "input"))
      (node (ref "R14") (pin "2") (pinfunction "2_2") (pintype "input"))
      (node (ref "U11") (pin "5") (pinfunction "B2_5") (pintype "unspecified"))
    )
    (net (code "55") (name "Net-(U11-C2)") (class "Default")
      (node (ref "LED1") (pin "2") (pinfunction "2_2") (pintype "unspecified"))
      (node (ref "U11") (pin "3") (pinfunction "C2_3") (pintype "unspecified"))
    )
    (net (code "56") (name "PRESSURE_EOC") (class "Default")
      (node (ref "IC3") (pin "24") (pinfunction "IO47_24") (pintype "bidirectional"))
      (node (ref "U1") (pin "8") (pinfunction "EOC_8") (pintype "bidirectional"))
    )
    (net (code "57") (name "PRESSURE_RESET") (class "Default")
      (node (ref "IC3") (pin "25") (pinfunction "IO48_25") (pintype "bidirectional"))
      (node (ref "R1") (pin "1") (pinfunction "1_1") (pintype "input"))
      (node (ref "U1") (pin "9") (pinfunction "RES_9") (pintype "bidirectional"))
    )
    (net (code "58") (name "PWM_BOMBA") (class "Default")
      (node (ref "IC3") (pin "38") (pinfunction "IO2_38") (pintype "bidirectional"))
      (node (ref "U4") (pin "6") (pinfunction "IN1_6") (pintype "unspecified"))
    )
    (net (code "59") (name "PWM_VALVULA") (class "Default")
      (node (ref "IC3") (pin "39") (pinfunction "IO1_39") (pintype "bidirectional"))
      (node (ref "U4") (pin "5") (pinfunction "IN2_5") (pintype "unspecified"))
    )
    (net (code "60") (name "RTS") (class "Default")
      (node (ref "IC2") (pin "24") (pinfunction "RTS_24") (pintype "bidirectional"))
      (node (ref "Q4") (pin "2") (pinfunction "E_2") (pintype "unspecified"))
      (node (ref "R22") (pin "2") (pinfunction "2_2") (pintype "input"))
    )
    (net (code "61") (name "SPI_MISO") (class "Default")
      (node (ref "IC1") (pin "25") (pinfunction "SPISOMI_25") (pintype "bidirectional"))
      (node (ref "IC3") (pin "9") (pinfunction "IO16_9") (pintype "bidirectional"))
    )
    (net (code "62") (name "SPI_MOSI") (class "Default")
      (node (ref "IC1") (pin "26") (pinfunction "SPISIMO_26") (pintype "bidirectional"))
      (node (ref "IC3") (pin "8") (pinfunction "IO15_8") (pintype "bidirectional"))
    )
    (net (code "63") (name "SPI_SCLK") (class "Default")
      (node (ref "IC1") (pin "24") (pinfunction "SCLK_24") (pintype "bidirectional"))
      (node (ref "IC3") (pin "10") (pinfunction "IO17_10") (pintype "bidirectional"))
    )
    (net (code "64") (name "TX_N") (class "Default")
      (node (ref "D5") (pin "3") (pinfunction "3_3") (pintype "unspecified"))
      (node (ref "DB1") (pin "3") (pinfunction "3_3") (pintype "input"))
      (node (ref "IC1") (pin "14") (pinfunction "TXN_14") (pintype "bidirectional"))
    )
    (net (code "65") (name "TX_P") (class "Default")
      (node (ref "D6") (pin "3") (pinfunction "3_3") (pintype "unspecified"))
      (node (ref "DB1") (pin "2") (pinfunction "2_2") (pintype "input"))
      (node (ref "IC1") (pin "15") (pinfunction "TXP_15") (pintype "bidirectional"))
    )
    (net (code "66") (name "UART_RX") (class "Default")
      (node (ref "IC3") (pin "36") (pinfunction "RXD0_36") (pintype "bidirectional"))
      (node (ref "R10") (pin "2") (pinfunction "2_2") (pintype "input"))
    )
    (net (code "67") (name "UART_TX") (class "Default")
      (node (ref "IC3") (pin "37") (pinfunction "TXD0_37") (pintype "bidirectional"))
      (node (ref "R34") (pin "2") (pinfunction "2_2") (pintype "input"))
    )
    (net (code "68") (name "VUSB_Pro") (class "Default")
      (node (ref "D8") (pin "2") (pinfunction "2_2") (pintype "bidirectional"))
      (node (ref "R19") (pin "2") (pinfunction "2_2") (pintype "input"))
      (node (ref "USB1") (pin "1") (pinfunction "VBUS_1") (pintype "unspecified"))
    )
    (net (code "69") (name "V_BAT") (class "Default")
      (node (ref "C18") (pin "2") (pinfunction "2_2") (pintype "unspecified"))
      (node (ref "C19") (pin "2") (pinfunction "2_2") (pintype "unspecified"))
      (node (ref "CN3") (pin "2") (pinfunction "2_2") (pintype "unspecified"))
      (node (ref "Q3") (pin "2") (pinfunction "S_2") (pintype "unspecified"))
      (node (ref "R8") (pin "1") (pinfunction "1_1") (pintype "input"))
      (node (ref "R9") (pin "1") (pinfunction "1_1") (pintype "input"))
      (node (ref "U5") (pin "10") (pinfunction "OUT_10") (pintype "output"))
    )
    (net (code "70") (name "V_DC") (class "Default")
      (node (ref "C39") (pin "1") (pinfunction "1_1") (pintype "unspecified"))
      (node (ref "C48") (pin "2") (pinfunction "2_2") (pintype "unspecified"))
      (node (ref "D7") (pin "2") (pinfunction "2_2") (pintype "bidirectional"))
      (node (ref "DC1") (pin "1") (pinfunction "1_1") (pintype "unspecified"))
      (node (ref "R12") (pin "2") (pinfunction "2_2") (pintype "unspecified"))
      (node (ref "R31") (pin "2") (pinfunction "2_2") (pintype "input"))
      (node (ref "U5") (pin "1") (pinfunction "IN_1") (pintype "passive"))
    )
    (net (code "71") (name "V_IN") (class "Default")
      (node (ref "C17") (pin "2") (pinfunction "2_2") (pintype "unspecified"))
      (node (ref "C42") (pin "2") (pinfunction "2_2") (pintype "unspecified"))
      (node (ref "Q3") (pin "3") (pinfunction "D_3") (pintype "unspecified"))
      (node (ref "R16") (pin "2") (pinfunction "2_2") (pintype "input"))
      (node (ref "R24") (pin "2") (pinfunction "2_2") (pintype "input"))
      (node (ref "U7") (pin "5") (pinfunction "VIN_5") (pintype "unspecified"))
    )
    (net (code "72") (name "Valvula_Out") (class "Default")
      (node (ref "CN2") (pin "1") (pinfunction "1_1") (pintype "unspecified"))
      (node (ref "D2") (pin "1") (pinfunction "1_1") (pintype "unspecified"))
      (node (ref "U4") (pin "3") (pinfunction "OUT2_3") (pintype "unspecified"))
    )
    (net (code "73") (name "unconnected-(D1-Pad2)") (class "Default")
      (node (ref "D1") (pin "2") (pinfunction "2_2") (pintype "unspecified+no_connect"))
    )
    (net (code "74") (name "unconnected-(D2-Pad2)") (class "Default")
      (node (ref "D2") (pin "2") (pinfunction "2_2") (pintype "unspecified+no_connect"))
    )
    (net (code "75") (name "unconnected-(DB1-Pad1)") (class "Default")
      (node (ref "DB1") (pin "1") (pinfunction "1_1") (pintype "input+no_connect"))
    )
    (net (code "76") (name "unconnected-(DB1-Pad4)") (class "Default")
      (node (ref "DB1") (pin "4") (pinfunction "4_4") (pintype "input+no_connect"))
    )
    (net (code "77") (name "unconnected-(DB1-Pad6)") (class "Default")
      (node (ref "DB1") (pin "6") (pinfunction "6_6") (pintype "input+no_connect"))
    )
    (net (code "78") (name "unconnected-(DB1-Pad8)") (class "Default")
      (node (ref "DB1") (pin "8") (pinfunction "8_8") (pintype "input+no_connect"))
    )
    (net (code "79") (name "unconnected-(IC1-CLKOUT-Pad30)") (class "Default")
      (node (ref "IC1") (pin "30") (pinfunction "CLKOUT_30") (pintype "bidirectional+no_connect"))
    )
    (net (code "80") (name "unconnected-(IC1-DNC_1-Pad5)") (class "Default")
      (node (ref "IC1") (pin "5") (pinfunction "DNC_1_5") (pintype "bidirectional+no_connect"))
    )
    (net (code "81") (name "unconnected-(IC1-DNC_2-Pad6)") (class "Default")
      (node (ref "IC1") (pin "6") (pinfunction "DNC_2_6") (pintype "bidirectional+no_connect"))
    )
    (net (code "82") (name "unconnected-(IC1-DNC_3-Pad10)") (class "Default")
      (node (ref "IC1") (pin "10") (pinfunction "DNC_3_10") (pintype "bidirectional+no_connect"))
    )
    (net (code "83") (name "unconnected-(IC1-LED_ALM-Pad22)") (class "Default")
      (node (ref "IC1") (pin "22") (pinfunction "LED_ALM_22") (pintype "bidirectional+no_connect"))
    )
    (net (code "84") (name "unconnected-(IC1-PD_ALM{slash}ADC_RESET-Pad23)") (class "Default")
      (node (ref "IC1") (pin "23") (pinfunction "PD_ALM/ADC_RESET_23") (pintype "bidirectional+no_connect"))
    )
    (net (code "85") (name "unconnected-(IC1-RXOUTN-Pad34)") (class "Default")
      (node (ref "IC1") (pin "34") (pinfunction "RXOUTN_34") (pintype "bidirectional+no_connect"))
    )
    (net (code "86") (name "unconnected-(IC1-RXOUTP-Pad35)") (class "Default")
      (node (ref "IC1") (pin "35") (pinfunction "RXOUTP_35") (pintype "bidirectional+no_connect"))
    )
    (net (code "87") (name "unconnected-(IC2-CHR0-Pad15)") (class "Default")
      (node (ref "IC2") (pin "15") (pinfunction "CHR0_15") (pintype "bidirectional+no_connect"))
    )
    (net (code "88") (name "unconnected-(IC2-CHR1-Pad14)") (class "Default")
      (node (ref "IC2") (pin "14") (pinfunction "CHR1_14") (pintype "bidirectional+no_connect"))
    )
    (net (code "89") (name "unconnected-(IC2-CHREN-Pad13)") (class "Default")
      (node (ref "IC2") (pin "13") (pinfunction "CHREN_13") (pintype "bidirectional+no_connect"))
    )
    (net (code "90") (name "unconnected-(IC2-CTS-Pad23)") (class "Default")
      (node (ref "IC2") (pin "23") (pinfunction "CTS_23") (pintype "bidirectional+no_connect"))
    )
    (net (code "91") (name "unconnected-(IC2-DCD-Pad1)") (class "Default")
      (node (ref "IC2") (pin "1") (pinfunction "DCD_1") (pintype "bidirectional+no_connect"))
    )
    (net (code "92") (name "unconnected-(IC2-DSR-Pad27)") (class "Default")
      (node (ref "IC2") (pin "27") (pinfunction "DSR_27") (pintype "bidirectional+no_connect"))
    )
    (net (code "93") (name "unconnected-(IC2-GPIO.0{slash}TXT-Pad19)") (class "Default")
      (node (ref "IC2") (pin "19") (pinfunction "GPIO.0/TXT_19") (pintype "bidirectional+no_connect"))
    )
    (net (code "94") (name "unconnected-(IC2-GPIO.1{slash}RXT-Pad18)") (class "Default")
      (node (ref "IC2") (pin "18") (pinfunction "GPIO.1/RXT_18") (pintype "bidirectional+no_connect"))
    )
    (net (code "95") (name "unconnected-(IC2-GPIO.2{slash}RS485-Pad17)") (class "Default")
      (node (ref "IC2") (pin "17") (pinfunction "GPIO.2/RS485_17") (pintype "bidirectional+no_connect"))
    )
    (net (code "96") (name "unconnected-(IC2-GPIO.3{slash}WAKEUP-Pad16)") (class "Default")
      (node (ref "IC2") (pin "16") (pinfunction "GPIO.3/WAKEUP_16") (pintype "bidirectional+no_connect"))
    )
    (net (code "97") (name "unconnected-(IC2-GPIO.4-Pad22)") (class "Default")
      (node (ref "IC2") (pin "22") (pinfunction "GPIO.4_22") (pintype "bidirectional+no_connect"))
    )
    (net (code "98") (name "unconnected-(IC2-GPIO.5-Pad21)") (class "Default")
      (node (ref "IC2") (pin "21") (pinfunction "GPIO.5_21") (pintype "bidirectional+no_connect"))
    )
    (net (code "99") (name "unconnected-(IC2-GPIO.6-Pad20)") (class "Default")
      (node (ref "IC2") (pin "20") (pinfunction "GPIO.6_20") (pintype "bidirectional+no_connect"))
    )
    (net (code "100") (name "unconnected-(IC2-NC-Pad10)") (class "Default")
      (node (ref "IC2") (pin "10") (pinfunction "NC_10") (pintype "bidirectional+no_connect"))
    )
    (net (code "101") (name "unconnected-(IC2-RI{slash}CLK-Pad2)") (class "Default")
      (node (ref "IC2") (pin "2") (pinfunction "RI/CLK_2") (pintype "bidirectional+no_connect"))
    )
    (net (code "102") (name "unconnected-(IC2-SUSPEND-Pad12)") (class "Default")
      (node (ref "IC2") (pin "12") (pinfunction "SUSPEND_12") (pintype "bidirectional+no_connect"))
    )
    (net (code "103") (name "unconnected-(IC3-IO3-Pad15)") (class "Default")
      (node (ref "IC3") (pin "15") (pinfunction "IO3_15") (pintype "bidirectional+no_connect"))
    )
    (net (code "104") (name "unconnected-(IC3-IO4-Pad4)") (class "Default")
      (node (ref "IC3") (pin "4") (pinfunction "IO4_4") (pintype "bidirectional+no_connect"))
    )
    (net (code "105") (name "unconnected-(IC3-IO11-Pad19)") (class "Default")
      (node (ref "IC3") (pin "19") (pinfunction "IO11_19") (pintype "bidirectional+no_connect"))
    )
    (net (code "106") (name "unconnected-(IC3-IO19-Pad13)") (class "Default")
      (node (ref "IC3") (pin "13") (pinfunction "IO19_13") (pintype "bidirectional+no_connect"))
    )
    (net (code "107") (name "unconnected-(IC3-IO20-Pad14)") (class "Default")
      (node (ref "IC3") (pin "14") (pinfunction "IO20_14") (pintype "bidirectional+no_connect"))
    )
    (net (code "108") (name "unconnected-(IC3-IO35-Pad28)") (class "Default")
      (node (ref "IC3") (pin "28") (pinfunction "IO35_28") (pintype "bidirectional+no_connect"))
    )
    (net (code "109") (name "unconnected-(IC3-IO36-Pad29)") (class "Default")
      (node (ref "IC3") (pin "29") (pinfunction "IO36_29") (pintype "bidirectional+no_connect"))
    )
    (net (code "110") (name "unconnected-(IC3-IO37-Pad30)") (class "Default")
      (node (ref "IC3") (pin "30") (pinfunction "IO37_30") (pintype "bidirectional+no_connect"))
    )
    (net (code "111") (name "unconnected-(IC3-IO38-Pad31)") (class "Default")
      (node (ref "IC3") (pin "31") (pinfunction "IO38_31") (pintype "bidirectional+no_connect"))
    )
    (net (code "112") (name "unconnected-(IC3-IO41-Pad34)") (class "Default")
      (node (ref "IC3") (pin "34") (pinfunction "IO41_34") (pintype "bidirectional+no_connect"))
    )
    (net (code "113") (name "unconnected-(IC3-IO42-Pad35)") (class "Default")
      (node (ref "IC3") (pin "35") (pinfunction "IO42_35") (pintype "bidirectional+no_connect"))
    )
    (net (code "114") (name "unconnected-(IC3-IO45-Pad26)") (class "Default")
      (node (ref "IC3") (pin "26") (pinfunction "IO45_26") (pintype "bidirectional+no_connect"))
    )
    (net (code "115") (name "unconnected-(IC3-IO46-Pad16)") (class "Default")
      (node (ref "IC3") (pin "16") (pinfunction "IO46_16") (pintype "bidirectional+no_connect"))
    )
    (net (code "116") (name "unconnected-(KEY1-Pad2)") (class "Default")
      (node (ref "KEY1") (pin "2") (pinfunction "2_2") (pintype "unspecified+no_connect"))
    )
    (net (code "117") (name "unconnected-(KEY1-Pad4)") (class "Default")
      (node (ref "KEY1") (pin "4") (pinfunction "4_4") (pintype "unspecified+no_connect"))
    )
    (net (code "118") (name "unconnected-(KEY2-Pad2)") (class "Default")
      (node (ref "KEY2") (pin "2") (pinfunction "2_2") (pintype "unspecified+no_connect"))
    )
    (net (code "119") (name "unconnected-(KEY2-Pad4)") (class "Default")
      (node (ref "KEY2") (pin "4") (pinfunction "4_4") (pintype "unspecified+no_connect"))
    )
    (net (code "120") (name "unconnected-(KEY3-Pad2)") (class "Default")
      (node (ref "KEY3") (pin "2") (pinfunction "2_2") (pintype "unspecified+no_connect"))
    )
    (net (code "121") (name "unconnected-(KEY3-Pad4)") (class "Default")
      (node (ref "KEY3") (pin "4") (pinfunction "4_4") (pintype "unspecified+no_connect"))
    )
    (net (code "122") (name "unconnected-(KEY4-Pad1)") (class "Default")
      (node (ref "KEY4") (pin "1") (pinfunction "1_1") (pintype "unspecified+no_connect"))
    )
    (net (code "123") (name "unconnected-(KEY4-Pad4)") (class "Default")
      (node (ref "KEY4") (pin "4") (pinfunction "4_4") (pintype "unspecified+no_connect"))
    )
    (net (code "124") (name "unconnected-(KEY6-Pad1)") (class "Default")
      (node (ref "KEY6") (pin "1") (pinfunction "1_1") (pintype "unspecified+no_connect"))
    )
    (net (code "125") (name "unconnected-(KEY6-Pad4)") (class "Default")
      (node (ref "KEY6") (pin "4") (pinfunction "4_4") (pintype "unspecified+no_connect"))
    )
    (net (code "126") (name "unconnected-(U1-MISO-Pad7)") (class "Default")
      (node (ref "U1") (pin "7") (pinfunction "MISO_7") (pintype "bidirectional+no_connect"))
    )
    (net (code "127") (name "unconnected-(U1-NC_1-Pad5)") (class "Default")
      (node (ref "U1") (pin "5") (pinfunction "NC_1_5") (pintype "bidirectional+no_connect"))
    )
    (net (code "128") (name "unconnected-(U1-NC_2-Pad11)") (class "Default")
      (node (ref "U1") (pin "11") (pinfunction "NC_2_11") (pintype "bidirectional+no_connect"))
    )
    (net (code "129") (name "unconnected-(U1-SS-Pad1)") (class "Default")
      (node (ref "U1") (pin "1") (pinfunction "SS_1") (pintype "bidirectional+no_connect"))
    )
    (net (code "130") (name "unconnected-(U5-NC-Pad6)") (class "Default")
      (node (ref "U5") (pin "6") (pinfunction "NC_6") (pintype "unspecified+no_connect"))
    )
    (net (code "131") (name "unconnected-(U6-NC-Pad1)") (class "Default")
      (node (ref "U6") (pin "1") (pinfunction "NC_1") (pintype "unspecified+no_connect"))
    )
    (net (code "132") (name "unconnected-(USB1-ID-Pad4)") (class "Default")
      (node (ref "USB1") (pin "4") (pinfunction "ID_4") (pintype "unspecified+no_connect"))
    )
  )
)
